# H2OhNo-v10.net
KiCad netlist of a schematic drawn in EAGLE
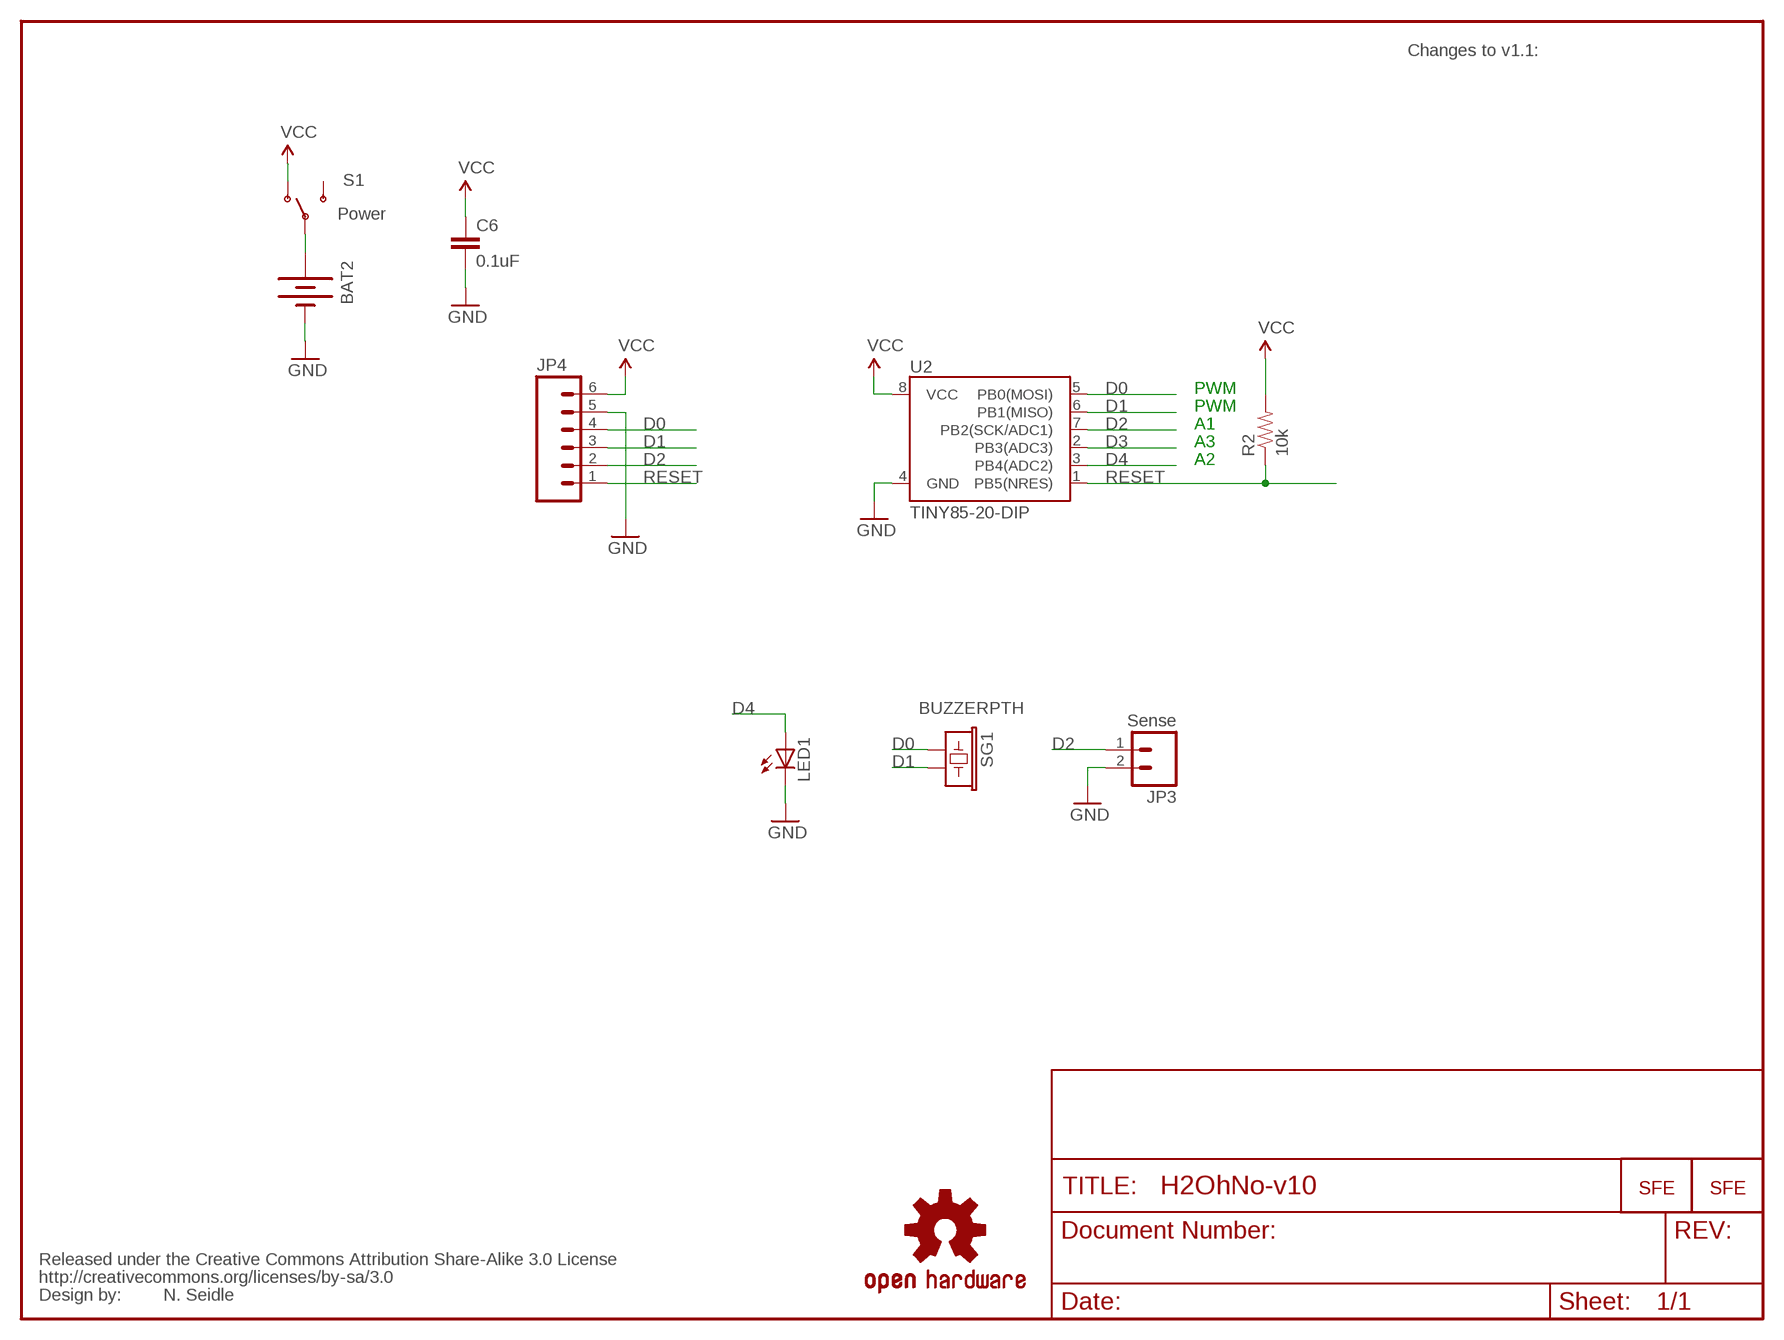
[diagram p0: schematic, sheet 1]

(export (version "E")
  (design (tool "Eeschema 10.0.6"))
  (components
    (comp (ref "BAT2")
      (value "BATTERY20PTH")
      (footprint "eagle-import:BATTCOM_20MM_PTH")
      (libsource (lib "eagle-import") (part "BATTERY20PTH"))
    )
    (comp (ref "C6")
      (value "0.1uF")
      (footprint "eagle-import:CAP-PTH-SMALL2")
      (libsource (lib "eagle-import") (part "CAPPTH2"))
    )
    (comp (ref "JP3")
      (value "Sense")
      (footprint "eagle-import:1X02")
      (libsource (lib "eagle-import") (part "M02PTH"))
    )
    (comp (ref "JP4")
      (value "M06SIP")
      (footprint "eagle-import:1X06")
      (libsource (lib "eagle-import") (part "M06SIP"))
    )
    (comp (ref "LED1")
      (value "LED5MM")
      (footprint "eagle-import:LED5MM")
      (libsource (lib "eagle-import") (part "LED5MM"))
    )
    (comp (ref "R2")
      (value "10k")
      (footprint "eagle-import:AXIAL-0.3")
      (libsource (lib "eagle-import") (part "RESISTORAXIAL-0.3"))
    )
    (comp (ref "S1")
      (value "Power")
      (footprint "eagle-import:SWITCH-SPDT")
      (libsource (lib "eagle-import") (part "SWITCH-SPDTPTH"))
    )
    (comp (ref "SG1")
      (value "BUZZERPTH")
      (footprint "eagle-import:BUZZER-12MM")
      (libsource (lib "eagle-import") (part "BUZZERPTH"))
    )
    (comp (ref "U$1")
      (value "LOGO-SFESK")
      (footprint "eagle-import:SFE-LOGO-FLAME")
      (libsource (lib "eagle-import") (part "LOGO-SFESK"))
    )
    (comp (ref "U$2")
      (value "CREATIVE_COMMONS")
      (footprint "eagle-import:CREATIVE_COMMONS")
      (libsource (lib "eagle-import") (part "CREATIVE_COMMONS"))
    )
    (comp (ref "U$4")
      (value "OSHW-LOGOS")
      (footprint "eagle-import:OSHW-LOGO-S")
      (libsource (lib "eagle-import") (part "OSHW-LOGOS"))
    )
    (comp (ref "U$5")
      (value "LOGO-SFENW2")
      (footprint "eagle-import:SFE-NEW-WEB")
      (libsource (lib "eagle-import") (part "LOGO-SFENW2"))
    )
    (comp (ref "U2")
      (value "TINY85-20-DIP")
      (footprint "eagle-import:DIP08")
      (fields (field (name "PROD_ID") "IC-09445"))
      (libsource (lib "eagle-import") (part "ATTINY45TINY85-20-DIP"))
    )
  )
  (nets
    (net (code "1") (name "/D0") (class "Default")
      (node (ref "JP4") (pin "4") (pinfunction "4_4") (pintype "passive"))
      (node (ref "SG1") (pin "+") (pinfunction "1_+") (pintype "passive"))
      (node (ref "U2") (pin "5") (pinfunction "PB0(MOSI)_5") (pintype "bidirectional"))
    )
    (net (code "2") (name "/D1") (class "Default")
      (node (ref "JP4") (pin "3") (pinfunction "3_3") (pintype "passive"))
      (node (ref "SG1") (pin "-") (pinfunction "2_-") (pintype "passive"))
      (node (ref "U2") (pin "6") (pinfunction "PB1(MISO)_6") (pintype "bidirectional"))
    )
    (net (code "3") (name "/D2") (class "Default")
      (node (ref "JP3") (pin "1") (pinfunction "1_1") (pintype "passive"))
      (node (ref "JP4") (pin "2") (pinfunction "2_2") (pintype "passive"))
      (node (ref "U2") (pin "7") (pinfunction "PB2(SCK/ADC1)_7") (pintype "bidirectional"))
    )
    (net (code "4") (name "/D3") (class "Default")
      (node (ref "U2") (pin "2") (pinfunction "PB3(ADC3)_2") (pintype "bidirectional"))
    )
    (net (code "5") (name "/D4") (class "Default")
      (node (ref "LED1") (pin "A") (pinfunction "A_A") (pintype "passive"))
      (node (ref "U2") (pin "3") (pinfunction "PB4(ADC2)_3") (pintype "bidirectional"))
    )
    (net (code "6") (name "/RESET") (class "Default")
      (node (ref "JP4") (pin "1") (pinfunction "1_1") (pintype "passive"))
      (node (ref "R2") (pin "P$1") (pinfunction "1_P$1") (pintype "passive"))
      (node (ref "U2") (pin "1") (pinfunction "PB5(NRES)_1") (pintype "bidirectional"))
    )
    (net (code "7") (name "GND") (class "Default")
      (node (ref "BAT2") (pin "2") (pinfunction "-_2") (pintype "power_in"))
      (node (ref "C6") (pin "2") (pinfunction "2_2") (pintype "passive"))
      (node (ref "JP3") (pin "2") (pinfunction "2_2") (pintype "passive"))
      (node (ref "JP4") (pin "5") (pinfunction "5_5") (pintype "passive"))
      (node (ref "LED1") (pin "K") (pinfunction "C_K") (pintype "passive"))
      (node (ref "U2") (pin "4") (pinfunction "GND_4") (pintype "bidirectional"))
    )
    (net (code "8") (name "Net-(BAT2-+)") (class "Default")
      (node (ref "BAT2") (pin "1") (pinfunction "+_1") (pintype "power_in"))
      (node (ref "S1") (pin "2") (pinfunction "P_2") (pintype "passive"))
    )
    (net (code "9") (name "VCC") (class "Default")
      (node (ref "C6") (pin "1") (pinfunction "1_1") (pintype "passive"))
      (node (ref "JP4") (pin "6") (pinfunction "6_6") (pintype "passive"))
      (node (ref "R2") (pin "P$2") (pinfunction "2_P$2") (pintype "passive"))
      (node (ref "S1") (pin "1") (pinfunction "O_1") (pintype "passive"))
      (node (ref "U2") (pin "8") (pinfunction "VCC_8") (pintype "bidirectional"))
    )
    (net (code "10") (name "unconnected-(S1-S-Pad3)") (class "Default")
      (node (ref "S1") (pin "3") (pinfunction "S_3") (pintype "passive"))
    )
  )
)
